# DashBoard_powerbox.net
KiCad netlist of a schematic drawn in EasyEDA
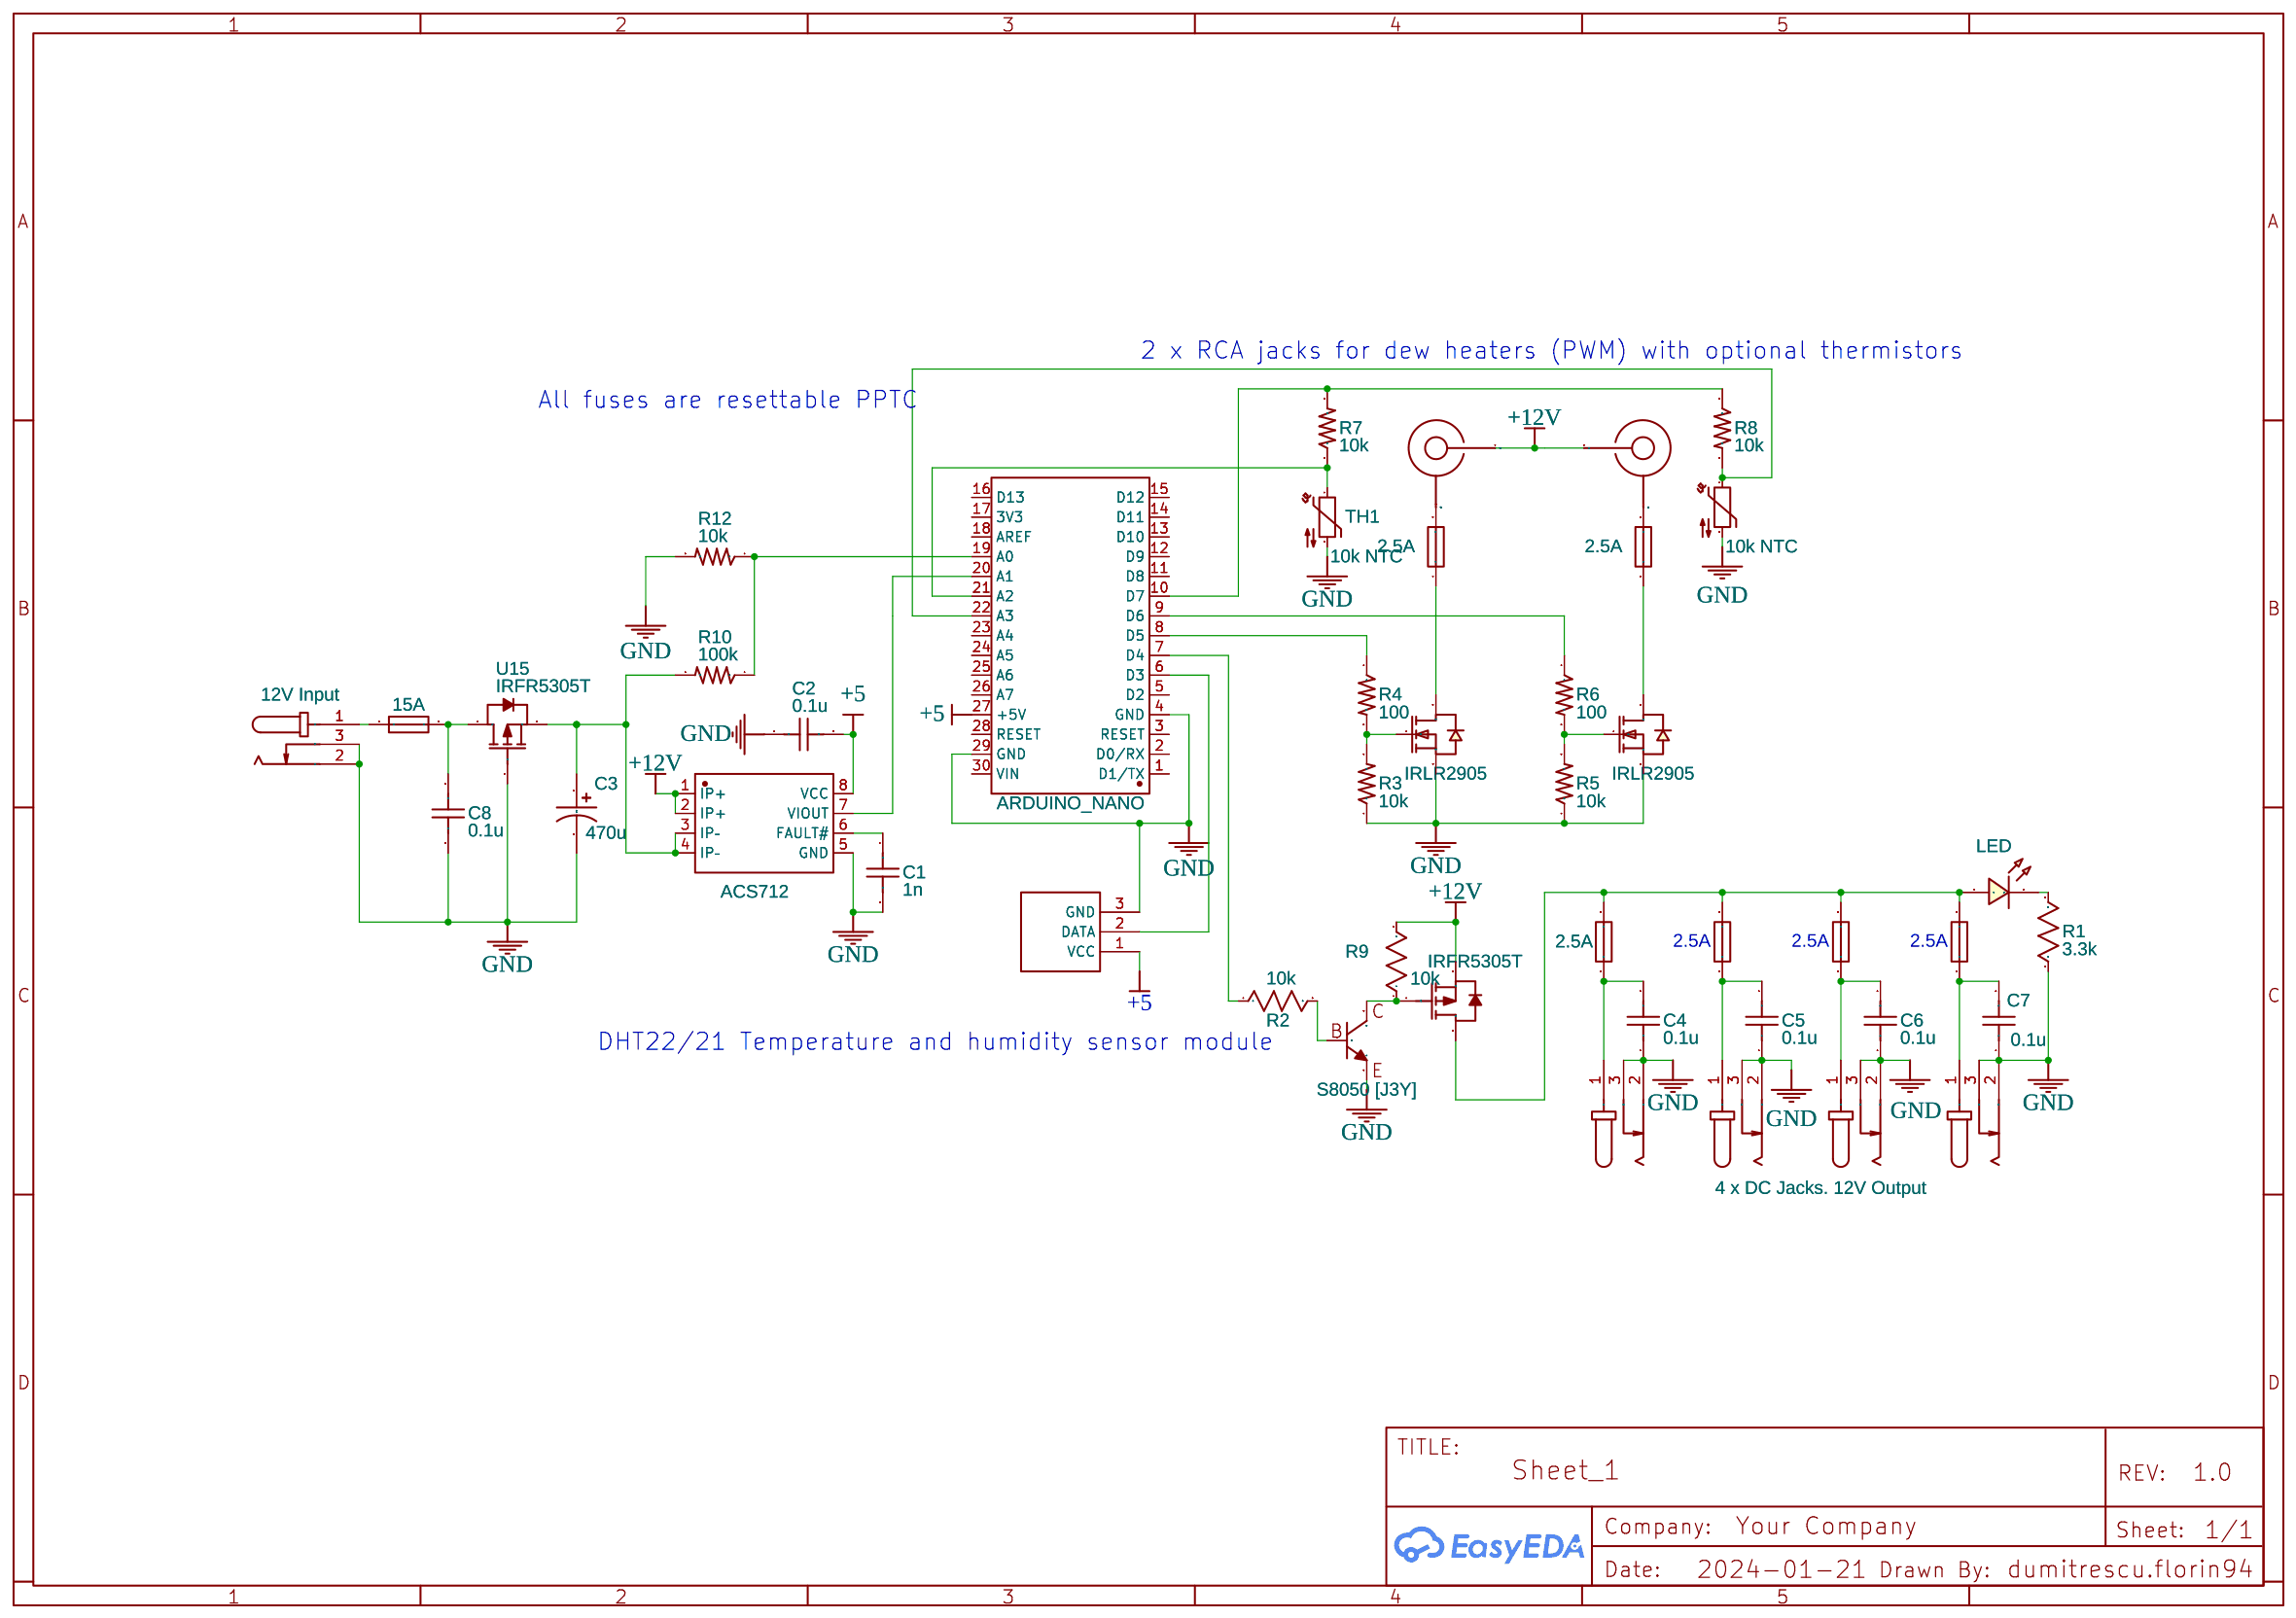
[diagram p0: schematic sheet]

(export (version "E")
  (design (tool "Eeschema 10.0.6"))
  (components
    (comp (ref "ACS712")
      (value "ACS71240LLCBTR-030B3")
      (fields (field (name "Manufacturer") "ALLEGRO(美国埃戈罗)"))
      (libsource (lib "") (part "ACS71240LLCBTR-030B3"))
    )
    (comp (ref "ARDUINO_NANO") (value "ARDUINO_NANO") (libsource (lib "") (part "ARDUINO_NANO")))
    (comp (ref "C1") (value "1n") (libsource (lib "") (part "C_0603_US")))
    (comp (ref "C2") (value "0.1u") (libsource (lib "") (part "C_0603_US_2")))
    (comp (ref "C3") (value "470u") (libsource (lib "") (part "CE_TH_D10.0×F5.0_US")))
    (comp (ref "C4") (value "0.1u") (libsource (lib "") (part "C_0603_US_1")))
    (comp (ref "C5") (value "0.1u") (libsource (lib "") (part "C_0603_US_1")))
    (comp (ref "C6") (value "0.1u") (libsource (lib "") (part "C_0603_US_1")))
    (comp (ref "C7") (value "0.1u") (libsource (lib "") (part "C_0603_US_1")))
    (comp (ref "C8") (value "0.1u") (libsource (lib "") (part "C_0603_US")))
    (comp (ref "F1")
      (value "15A")
      (fields
        (field (name "Manufacturer Part") "0326025.MXP")
        (field (name "Manufacturer") "Littelfuse(美国力特)")
      )
      (libsource (lib "") (part "0326025.MXP_1"))
    )
    (comp (ref "F2")
      (value "2.5A")
      (fields
        (field (name "Manufacturer Part") "0326025.MXP")
        (field (name "Manufacturer") "Littelfuse(美国力特)")
      )
      (libsource (lib "") (part "0326025.MXP"))
    )
    (comp (ref "F3")
      (value "2A")
      (fields
        (field (name "Manufacturer Part") "0326025.MXP")
        (field (name "Manufacturer") "Littelfuse(美国力特)")
      )
      (libsource (lib "") (part "0326025.MXP"))
    )
    (comp (ref "F4")
      (value "2A")
      (fields
        (field (name "Manufacturer Part") "0326025.MXP")
        (field (name "Manufacturer") "Littelfuse(美国力特)")
      )
      (libsource (lib "") (part "0326025.MXP"))
    )
    (comp (ref "F5")
      (value "2A")
      (fields
        (field (name "Manufacturer Part") "0326025.MXP")
        (field (name "Manufacturer") "Littelfuse(美国力特)")
      )
      (libsource (lib "") (part "0326025.MXP"))
    )
    (comp (ref "F6")
      (value "2.5A")
      (fields
        (field (name "Manufacturer Part") "0326025.MXP")
        (field (name "Manufacturer") "Littelfuse(美国力特)")
      )
      (libsource (lib "") (part "0326025.MXP"))
    )
    (comp (ref "F7")
      (value "2.5A")
      (fields
        (field (name "Manufacturer Part") "0326025.MXP")
        (field (name "Manufacturer") "Littelfuse(美国力特)")
      )
      (libsource (lib "") (part "0326025.MXP"))
    )
    (comp (ref "IN1")
      (value "12V Input")
      (fields (field (name "Manufacturer Part") "POWER-JACK") (field (name "Manufacturer") "索峰"))
      (libsource (lib "") (part "POWER-JACK_1"))
    )
    (comp (ref "LED1")
      (value "LED")
      (fields
        (field (name "Manufacturer Part") "333-2SURD/S530-A3")
        (field (name "Manufacturer") "EVERLIGHT(台湾亿光)")
      )
      (libsource (lib "") (part "LED-TH-5mm_R"))
    )
    (comp (ref "R1") (value "3.3k") (libsource (lib "") (part "R_0201_US")))
    (comp (ref "R2") (value "10k") (libsource (lib "") (part "R_0201_US_1")))
    (comp (ref "R3") (value "10k") (libsource (lib "") (part "RESISTORPTH-16W")))
    (comp (ref "R4") (value "100") (libsource (lib "") (part "RESISTORPTH-16W_1")))
    (comp (ref "R5") (value "10k") (libsource (lib "") (part "RESISTORPTH-16W")))
    (comp (ref "R6") (value "100") (libsource (lib "") (part "RESISTORPTH-16W_1")))
    (comp (ref "R7") (value "10k") (libsource (lib "") (part "RESISTORPTH-16W")))
    (comp (ref "R8") (value "10k") (libsource (lib "") (part "RESISTORPTH-16W_1")))
    (comp (ref "R9") (value "10k") (libsource (lib "") (part "R_0201_US")))
    (comp (ref "R10") (value "100k") (libsource (lib "") (part "RESISTORPTH-16W_2")))
    (comp (ref "R12") (value "10k") (libsource (lib "") (part "RESISTORPTH-16W_2")))
    (comp (ref "TH1") (value "10k NTC") (libsource (lib "") (part "Thermistor_NTC")))
    (comp (ref "TH2") (value "10k NTC") (libsource (lib "") (part "Thermistor_NTC")))
    (comp (ref "U1") (value "input left SE") (libsource (lib "") (part "RCA Phono")))
    (comp (ref "U2") (value "input left SE") (libsource (lib "") (part "RCA Phono_1")))
    (comp (ref "U3")
      (value "IRFR5305T")
      (fields (field (name "Manufacturer") "HXY MOSFET(华轩阳电子)"))
      (libsource (lib "") (part "IRFR5305T"))
    )
    (comp (ref "U5")
      (value "IRLR2905")
      (fields (field (name "Manufacturer") "TECH PUBLIC(台舟)"))
      (libsource (lib "") (part "IRLR2905"))
    )
    (comp (ref "U8")
      (value "POWER-JACK")
      (fields (field (name "Manufacturer") "索峰"))
      (libsource (lib "") (part "POWER-JACK"))
    )
    (comp (ref "U9")
      (value "POWER-JACK")
      (fields (field (name "Manufacturer") "索峰"))
      (libsource (lib "") (part "POWER-JACK"))
    )
    (comp (ref "U10")
      (value "POWER-JACK")
      (fields (field (name "Manufacturer") "索峰"))
      (libsource (lib "") (part "POWER-JACK"))
    )
    (comp (ref "U11")
      (value "4 x DC Jacks. 12V Output")
      (fields (field (name "Manufacturer Part") "POWER-JACK") (field (name "Manufacturer") "索峰"))
      (libsource (lib "") (part "POWER-JACK"))
    )
    (comp (ref "U12")
      (value "IRLR2905")
      (fields (field (name "Manufacturer") "TECH PUBLIC(台舟)"))
      (libsource (lib "") (part "IRLR2905"))
    )
    (comp (ref "U13") (value "DHT22-MODULE") (libsource (lib "") (part "DHT22-MODULE")))
    (comp (ref "U14")
      (value "S8050 [J3Y]")
      (fields (field (name "Manufacturer Part") "S8050") (field (name "Manufacturer") "JUXING(钜兴)"))
      (libsource (lib "") (part "S8050 [J3Y]"))
    )
    (comp (ref "U15")
      (value "IRFR5305T")
      (fields (field (name "Manufacturer") "HXY MOSFET(华轩阳电子)"))
      (libsource (lib "") (part "IRFR5305T_1"))
    )
  )
  (nets
    (net (code "1") (name "+5") (class "Default")
      (node (ref "ACS712") (pin "8") (pinfunction "VCC_8") (pintype "unspecified"))
      (node (ref "ARDUINO_NANO") (pin "27") (pinfunction "+5V_27") (pintype "unspecified"))
      (node (ref "C2") (pin "2") (pinfunction "2_2") (pintype "unspecified"))
      (node (ref "U13") (pin "1") (pinfunction "VCC_1") (pintype "unspecified"))
    )
    (net (code "2") (name "+12V") (class "Default")
      (node (ref "ACS712") (pin "1") (pinfunction "IP+_1") (pintype "unspecified"))
      (node (ref "ACS712") (pin "2") (pinfunction "IP+_2") (pintype "unspecified"))
      (node (ref "R9") (pin "2") (pinfunction "2_2") (pintype "unspecified"))
      (node (ref "U1") (pin "1") (pinfunction "SIG_1") (pintype "unspecified"))
      (node (ref "U2") (pin "1") (pinfunction "SIG_1") (pintype "unspecified"))
      (node (ref "U3") (pin "3") (pinfunction "S_3") (pintype "unspecified"))
    )
    (net (code "3") (name "GND") (class "Default")
      (node (ref "ACS712") (pin "5") (pinfunction "GND_5") (pintype "unspecified"))
      (node (ref "ARDUINO_NANO") (pin "29") (pinfunction "GND_29") (pintype "unspecified"))
      (node (ref "ARDUINO_NANO") (pin "4") (pinfunction "GND_4") (pintype "unspecified"))
      (node (ref "C1") (pin "2") (pinfunction "2_2") (pintype "unspecified"))
      (node (ref "C2") (pin "1") (pinfunction "1_1") (pintype "unspecified"))
      (node (ref "C3") (pin "2") (pinfunction "2_2") (pintype "unspecified"))
      (node (ref "C4") (pin "1") (pinfunction "1_1") (pintype "unspecified"))
      (node (ref "C5") (pin "1") (pinfunction "1_1") (pintype "unspecified"))
      (node (ref "C6") (pin "1") (pinfunction "1_1") (pintype "unspecified"))
      (node (ref "C7") (pin "1") (pinfunction "1_1") (pintype "unspecified"))
      (node (ref "C8") (pin "2") (pinfunction "2_2") (pintype "unspecified"))
      (node (ref "IN1") (pin "2") (pinfunction "2_2") (pintype "unspecified"))
      (node (ref "IN1") (pin "3") (pinfunction "3_3") (pintype "unspecified"))
      (node (ref "R1") (pin "1") (pinfunction "1_1") (pintype "unspecified"))
      (node (ref "R12") (pin "2") (pinfunction "2_2") (pintype "unspecified"))
      (node (ref "R3") (pin "1") (pinfunction "1_1") (pintype "unspecified"))
      (node (ref "R5") (pin "1") (pinfunction "1_1") (pintype "unspecified"))
      (node (ref "TH1") (pin "2") (pintype "unspecified"))
      (node (ref "TH2") (pin "2") (pintype "unspecified"))
      (node (ref "U10") (pin "2") (pinfunction "2_2") (pintype "unspecified"))
      (node (ref "U10") (pin "3") (pinfunction "3_3") (pintype "unspecified"))
      (node (ref "U11") (pin "2") (pinfunction "2_2") (pintype "unspecified"))
      (node (ref "U11") (pin "3") (pinfunction "3_3") (pintype "unspecified"))
      (node (ref "U12") (pin "3") (pinfunction "S_3") (pintype "unspecified"))
      (node (ref "U13") (pin "3") (pinfunction "GND_3") (pintype "unspecified"))
      (node (ref "U14") (pin "2") (pinfunction "E_2") (pintype "unspecified"))
      (node (ref "U15") (pin "1") (pinfunction "G_1") (pintype "unspecified"))
      (node (ref "U5") (pin "3") (pinfunction "S_3") (pintype "unspecified"))
      (node (ref "U8") (pin "2") (pinfunction "2_2") (pintype "unspecified"))
      (node (ref "U8") (pin "3") (pinfunction "3_3") (pintype "unspecified"))
      (node (ref "U9") (pin "2") (pinfunction "2_2") (pintype "unspecified"))
      (node (ref "U9") (pin "3") (pinfunction "3_3") (pintype "unspecified"))
    )
    (net (code "4") (name "Net-(ACS712-FAULT#)") (class "Default")
      (node (ref "ACS712") (pin "6") (pinfunction "FAULT#_6") (pintype "unspecified"))
      (node (ref "C1") (pin "1") (pinfunction "1_1") (pintype "unspecified"))
    )
    (net (code "5") (name "Net-(ACS712-VIOUT)") (class "Default")
      (node (ref "ACS712") (pin "7") (pinfunction "VIOUT_7") (pintype "unspecified"))
      (node (ref "ARDUINO_NANO") (pin "20") (pinfunction "A1_20") (pintype "unspecified"))
    )
    (net (code "6") (name "Net-(ARDUINO_NANO-A0)") (class "Default")
      (node (ref "ARDUINO_NANO") (pin "19") (pinfunction "A0_19") (pintype "unspecified"))
      (node (ref "R10") (pin "1") (pinfunction "1_1") (pintype "unspecified"))
      (node (ref "R12") (pin "1") (pinfunction "1_1") (pintype "unspecified"))
    )
    (net (code "7") (name "Net-(ARDUINO_NANO-A2)") (class "Default")
      (node (ref "ARDUINO_NANO") (pin "21") (pinfunction "A2_21") (pintype "unspecified"))
      (node (ref "R7") (pin "1") (pinfunction "1_1") (pintype "unspecified"))
      (node (ref "TH1") (pin "1") (pintype "unspecified"))
    )
    (net (code "8") (name "Net-(ARDUINO_NANO-A3)") (class "Default")
      (node (ref "ARDUINO_NANO") (pin "22") (pinfunction "A3_22") (pintype "unspecified"))
      (node (ref "R8") (pin "2") (pinfunction "2_2") (pintype "unspecified"))
      (node (ref "TH2") (pin "1") (pintype "unspecified"))
    )
    (net (code "9") (name "Net-(ARDUINO_NANO-D3)") (class "Default")
      (node (ref "ARDUINO_NANO") (pin "6") (pinfunction "D3_6") (pintype "unspecified"))
      (node (ref "U13") (pin "2") (pinfunction "DATA_2") (pintype "unspecified"))
    )
    (net (code "10") (name "Net-(ARDUINO_NANO-D4)") (class "Default")
      (node (ref "ARDUINO_NANO") (pin "7") (pinfunction "D4_7") (pintype "unspecified"))
      (node (ref "R2") (pin "1") (pinfunction "1_1") (pintype "unspecified"))
    )
    (net (code "11") (name "Net-(ARDUINO_NANO-D5)") (class "Default")
      (node (ref "ARDUINO_NANO") (pin "8") (pinfunction "D5_8") (pintype "unspecified"))
      (node (ref "R4") (pin "1") (pinfunction "1_1") (pintype "unspecified"))
    )
    (net (code "12") (name "Net-(ARDUINO_NANO-D6)") (class "Default")
      (node (ref "ARDUINO_NANO") (pin "9") (pinfunction "D6_9") (pintype "unspecified"))
      (node (ref "R6") (pin "1") (pinfunction "1_1") (pintype "unspecified"))
    )
    (net (code "13") (name "Net-(ARDUINO_NANO-D7)") (class "Default")
      (node (ref "ARDUINO_NANO") (pin "10") (pinfunction "D7_10") (pintype "unspecified"))
      (node (ref "R7") (pin "2") (pinfunction "2_2") (pintype "unspecified"))
      (node (ref "R8") (pin "1") (pinfunction "1_1") (pintype "unspecified"))
    )
    (net (code "14") (name "Net-(C4-Pad2)") (class "Default")
      (node (ref "C4") (pin "2") (pinfunction "2_2") (pintype "unspecified"))
      (node (ref "F2") (pin "1") (pinfunction "1_1") (pintype "unspecified"))
      (node (ref "U8") (pin "1") (pinfunction "1_1") (pintype "unspecified"))
    )
    (net (code "15") (name "Net-(C5-Pad2)") (class "Default")
      (node (ref "C5") (pin "2") (pinfunction "2_2") (pintype "unspecified"))
      (node (ref "F3") (pin "1") (pinfunction "1_1") (pintype "unspecified"))
      (node (ref "U9") (pin "1") (pinfunction "1_1") (pintype "unspecified"))
    )
    (net (code "16") (name "Net-(C6-Pad2)") (class "Default")
      (node (ref "C6") (pin "2") (pinfunction "2_2") (pintype "unspecified"))
      (node (ref "F4") (pin "1") (pinfunction "1_1") (pintype "unspecified"))
      (node (ref "U10") (pin "1") (pinfunction "1_1") (pintype "unspecified"))
    )
    (net (code "17") (name "Net-(C7-Pad2)") (class "Default")
      (node (ref "C7") (pin "2") (pinfunction "2_2") (pintype "unspecified"))
      (node (ref "F5") (pin "1") (pinfunction "1_1") (pintype "unspecified"))
      (node (ref "U11") (pin "1") (pinfunction "1_1") (pintype "unspecified"))
    )
    (net (code "18") (name "Net-(F1-Pad1)") (class "Default")
      (node (ref "F1") (pin "1") (pinfunction "1_1") (pintype "unspecified"))
      (node (ref "IN1") (pin "1") (pinfunction "1_1") (pintype "unspecified"))
    )
    (net (code "19") (name "Net-(LED1-Pad2)") (class "Default")
      (node (ref "LED1") (pin "2") (pinfunction "2_2") (pintype "unspecified"))
      (node (ref "R1") (pin "2") (pinfunction "2_2") (pintype "unspecified"))
    )
    (net (code "20") (name "Net-(U1-GND)") (class "Default")
      (node (ref "F6") (pin "2") (pinfunction "2_2") (pintype "unspecified"))
      (node (ref "U1") (pin "2") (pinfunction "GND_2") (pintype "unspecified"))
    )
    (net (code "21") (name "Net-(U2-GND)") (class "Default")
      (node (ref "F7") (pin "2") (pinfunction "2_2") (pintype "unspecified"))
      (node (ref "U2") (pin "2") (pinfunction "GND_2") (pintype "unspecified"))
    )
    (net (code "22") (name "Net-(U3-D)") (class "Default")
      (node (ref "F2") (pin "2") (pinfunction "2_2") (pintype "unspecified"))
      (node (ref "F3") (pin "2") (pinfunction "2_2") (pintype "unspecified"))
      (node (ref "F4") (pin "2") (pinfunction "2_2") (pintype "unspecified"))
      (node (ref "F5") (pin "2") (pinfunction "2_2") (pintype "unspecified"))
      (node (ref "LED1") (pin "1") (pinfunction "1_1") (pintype "unspecified"))
      (node (ref "U3") (pin "2") (pinfunction "D_2") (pintype "unspecified"))
    )
    (net (code "23") (name "Net-(U5-D)") (class "Default")
      (node (ref "F6") (pin "1") (pinfunction "1_1") (pintype "unspecified"))
      (node (ref "U5") (pin "2") (pinfunction "D_2") (pintype "unspecified"))
    )
    (net (code "24") (name "Net-(U5-G)") (class "Default")
      (node (ref "R3") (pin "2") (pinfunction "2_2") (pintype "unspecified"))
      (node (ref "R4") (pin "2") (pinfunction "2_2") (pintype "unspecified"))
      (node (ref "U5") (pin "1") (pinfunction "G_1") (pintype "unspecified"))
    )
    (net (code "25") (name "Net-(U12-D)") (class "Default")
      (node (ref "F7") (pin "1") (pinfunction "1_1") (pintype "unspecified"))
      (node (ref "U12") (pin "2") (pinfunction "D_2") (pintype "unspecified"))
    )
    (net (code "26") (name "Net-(U12-G)") (class "Default")
      (node (ref "R5") (pin "2") (pinfunction "2_2") (pintype "unspecified"))
      (node (ref "R6") (pin "2") (pinfunction "2_2") (pintype "unspecified"))
      (node (ref "U12") (pin "1") (pinfunction "G_1") (pintype "unspecified"))
    )
    (net (code "27") (name "Net-(U14-B)") (class "Default")
      (node (ref "R2") (pin "2") (pinfunction "2_2") (pintype "unspecified"))
      (node (ref "U14") (pin "1") (pinfunction "B_1") (pintype "unspecified"))
    )
    (net (code "28") (name "Net-(U14-C)") (class "Default")
      (node (ref "R9") (pin "1") (pinfunction "1_1") (pintype "unspecified"))
      (node (ref "U14") (pin "3") (pinfunction "C_3") (pintype "unspecified"))
      (node (ref "U3") (pin "1") (pinfunction "G_1") (pintype "unspecified"))
    )
    (net (code "29") (name "Net-(U15-D)") (class "Default")
      (node (ref "C8") (pin "1") (pinfunction "1_1") (pintype "unspecified"))
      (node (ref "F1") (pin "2") (pinfunction "2_2") (pintype "unspecified"))
      (node (ref "U15") (pin "2") (pinfunction "D_2") (pintype "unspecified"))
    )
    (net (code "30") (name "Net-(U15-S)") (class "Default")
      (node (ref "ACS712") (pin "3") (pinfunction "IP–_3") (pintype "unspecified"))
      (node (ref "ACS712") (pin "4") (pinfunction "IP–_4") (pintype "unspecified"))
      (node (ref "C3") (pin "1") (pinfunction "1_1") (pintype "unspecified"))
      (node (ref "R10") (pin "2") (pinfunction "2_2") (pintype "unspecified"))
      (node (ref "U15") (pin "3") (pinfunction "S_3") (pintype "unspecified"))
    )
    (net (code "31") (name "unconnected-(ARDUINO_NANO-3V3-Pad17)") (class "Default")
      (node (ref "ARDUINO_NANO") (pin "17") (pinfunction "3V3_17") (pintype "unspecified"))
    )
    (net (code "32") (name "unconnected-(ARDUINO_NANO-A4-Pad23)") (class "Default")
      (node (ref "ARDUINO_NANO") (pin "23") (pinfunction "A4_23") (pintype "unspecified"))
    )
    (net (code "33") (name "unconnected-(ARDUINO_NANO-A5-Pad24)") (class "Default")
      (node (ref "ARDUINO_NANO") (pin "24") (pinfunction "A5_24") (pintype "unspecified"))
    )
    (net (code "34") (name "unconnected-(ARDUINO_NANO-A6-Pad25)") (class "Default")
      (node (ref "ARDUINO_NANO") (pin "25") (pinfunction "A6_25") (pintype "unspecified"))
    )
    (net (code "35") (name "unconnected-(ARDUINO_NANO-A7-Pad26)") (class "Default")
      (node (ref "ARDUINO_NANO") (pin "26") (pinfunction "A7_26") (pintype "unspecified"))
    )
    (net (code "36") (name "unconnected-(ARDUINO_NANO-AREF-Pad18)") (class "Default")
      (node (ref "ARDUINO_NANO") (pin "18") (pinfunction "AREF_18") (pintype "unspecified"))
    )
    (net (code "37") (name "unconnected-(ARDUINO_NANO-D0{slash}RX-Pad2)") (class "Default")
      (node (ref "ARDUINO_NANO") (pin "2") (pinfunction "D0/RX_2") (pintype "unspecified"))
    )
    (net (code "38") (name "unconnected-(ARDUINO_NANO-D1{slash}TX-Pad1)") (class "Default")
      (node (ref "ARDUINO_NANO") (pin "1") (pinfunction "D1/TX_1") (pintype "unspecified"))
    )
    (net (code "39") (name "unconnected-(ARDUINO_NANO-D2-Pad5)") (class "Default")
      (node (ref "ARDUINO_NANO") (pin "5") (pinfunction "D2_5") (pintype "unspecified"))
    )
    (net (code "40") (name "unconnected-(ARDUINO_NANO-D8-Pad11)") (class "Default")
      (node (ref "ARDUINO_NANO") (pin "11") (pinfunction "D8_11") (pintype "unspecified"))
    )
    (net (code "41") (name "unconnected-(ARDUINO_NANO-D9-Pad12)") (class "Default")
      (node (ref "ARDUINO_NANO") (pin "12") (pinfunction "D9_12") (pintype "unspecified"))
    )
    (net (code "42") (name "unconnected-(ARDUINO_NANO-D10-Pad13)") (class "Default")
      (node (ref "ARDUINO_NANO") (pin "13") (pinfunction "D10_13") (pintype "unspecified"))
    )
    (net (code "43") (name "unconnected-(ARDUINO_NANO-D11-Pad14)") (class "Default")
      (node (ref "ARDUINO_NANO") (pin "14") (pinfunction "D11_14") (pintype "unspecified"))
    )
    (net (code "44") (name "unconnected-(ARDUINO_NANO-D12-Pad15)") (class "Default")
      (node (ref "ARDUINO_NANO") (pin "15") (pinfunction "D12_15") (pintype "unspecified"))
    )
    (net (code "45") (name "unconnected-(ARDUINO_NANO-D13-Pad16)") (class "Default")
      (node (ref "ARDUINO_NANO") (pin "16") (pinfunction "D13_16") (pintype "unspecified"))
    )
    (net (code "46") (name "unconnected-(ARDUINO_NANO-RESET-Pad3)") (class "Default")
      (node (ref "ARDUINO_NANO") (pin "3") (pinfunction "RESET_3") (pintype "unspecified"))
    )
    (net (code "47") (name "unconnected-(ARDUINO_NANO-RESET-Pad28)") (class "Default")
      (node (ref "ARDUINO_NANO") (pin "28") (pinfunction "RESET_28") (pintype "unspecified"))
    )
    (net (code "48") (name "unconnected-(ARDUINO_NANO-VIN-Pad30)") (class "Default")
      (node (ref "ARDUINO_NANO") (pin "30") (pinfunction "VIN_30") (pintype "unspecified"))
    )
  )
)
